# Carrier_Cancellation_HP.net
KiCad netlist of a schematic drawn in Altium Designer
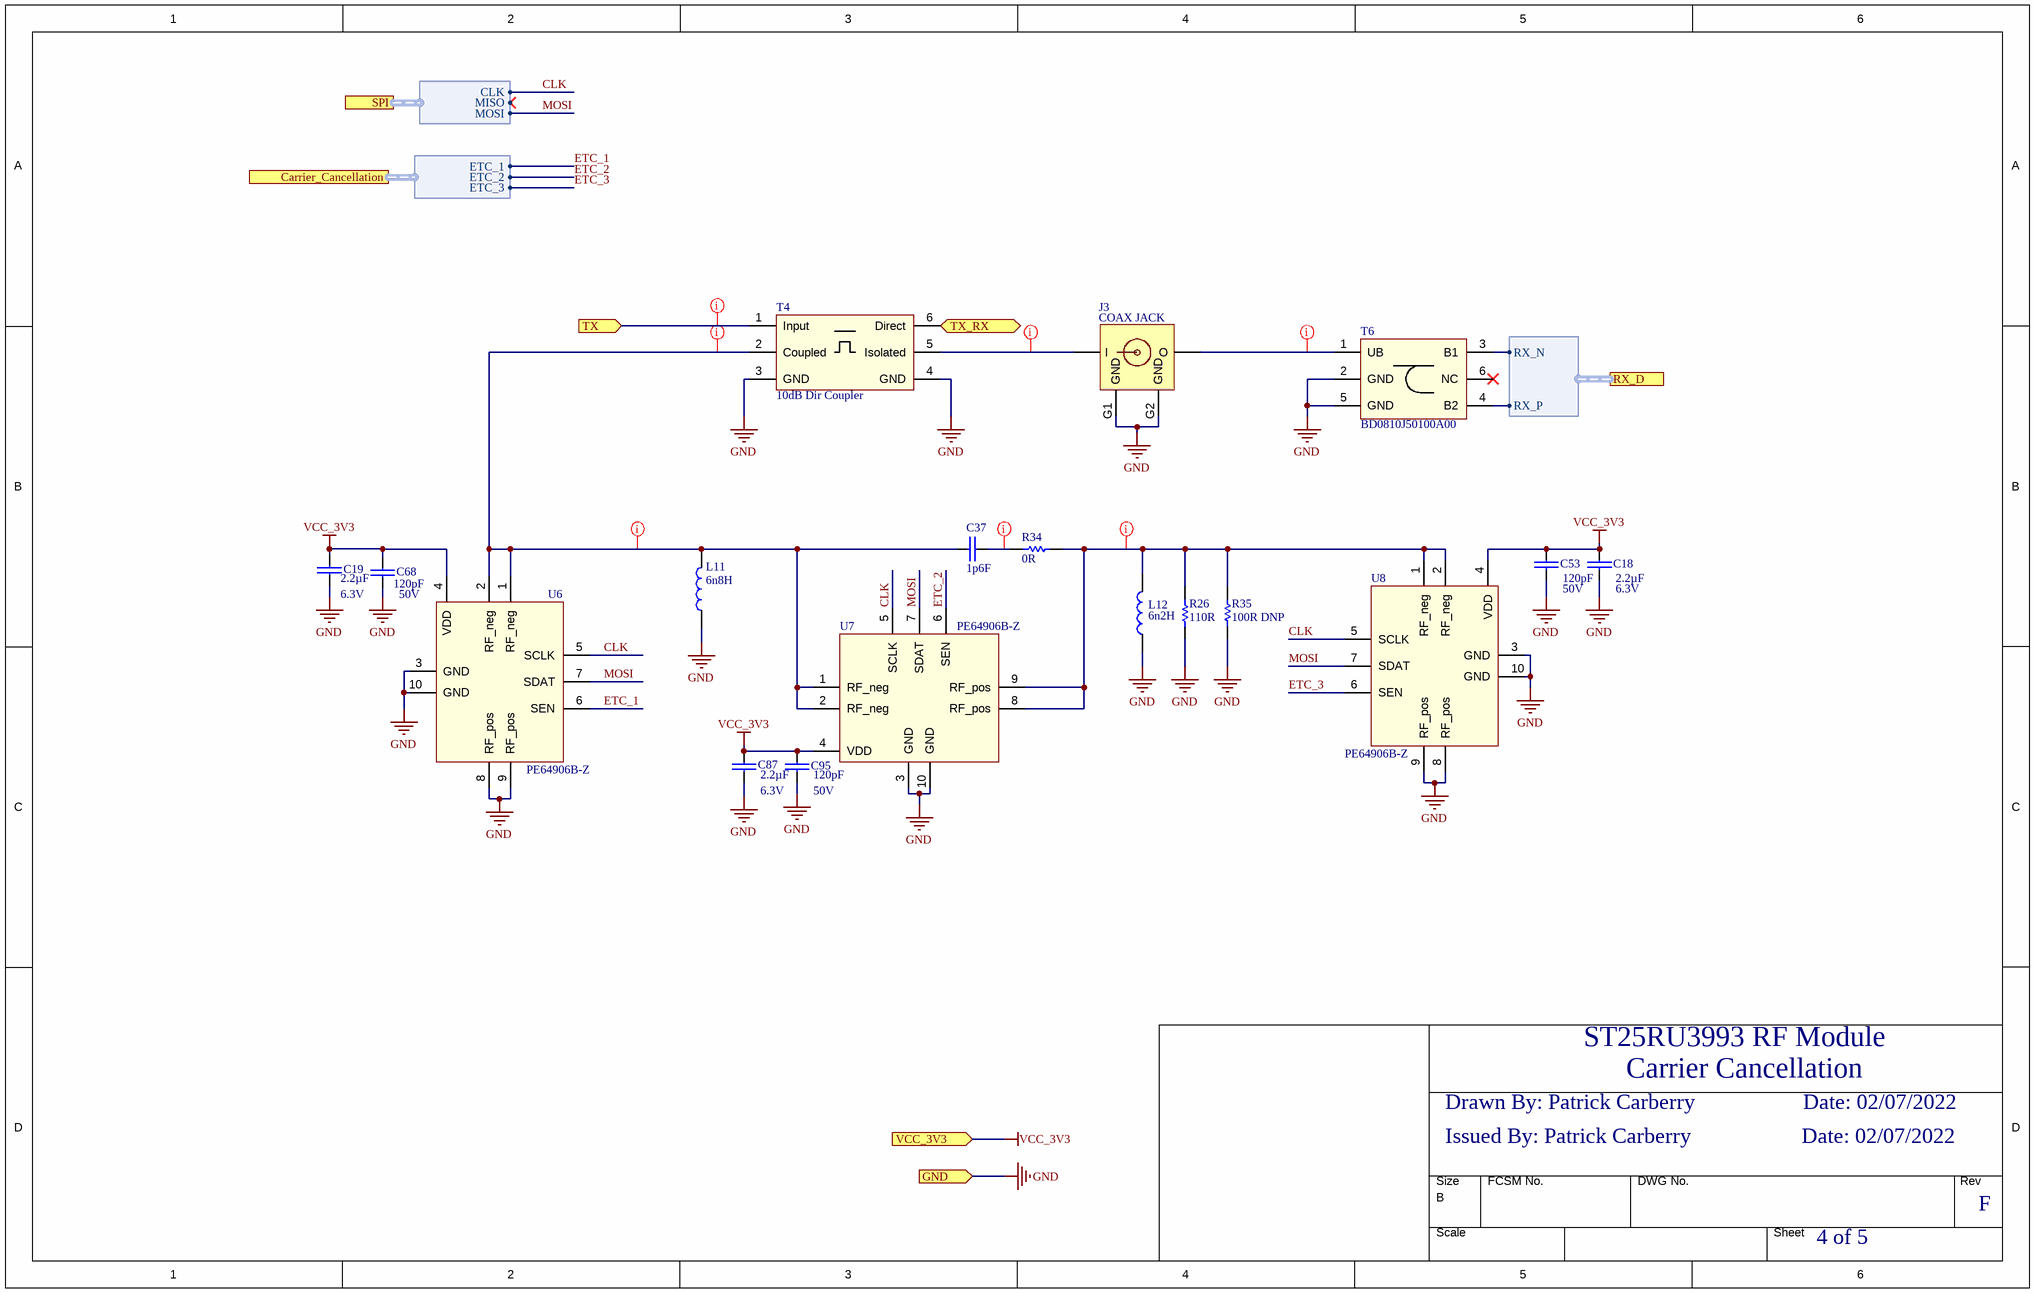
[diagram p0: Carrier_Cancellation_HP.SchDoc]

(export (version "E")
  (design (tool "Eeschema 10.0.6"))
  (components
    (comp (ref "C18")
      (value "C0402C225K9PAC7867")
      (footprint "C0402-RF")
      (description "CAP_2.2UF_6.3V_10%_X5R_0402")
      (fields
        (field (name "CAPACITANCE") "2.2µF")
        (field (name "TOLERANCE") "10%")
        (field (name "VOLTAGE - RATED") "6.3V")
        (field (name "MANUFACTURER") "KEMET")
      )
      (libsource (lib "ST25RU3993_RF_MODULE") (part "CAP_2.2UF_6.3V_10%_X5R_0402"))
    )
    (comp (ref "C19")
      (value "C0402C225K9PAC7867")
      (footprint "C0402-RF")
      (description "CAP_2.2UF_6.3V_10%_X5R_0402")
      (fields
        (field (name "CAPACITANCE") "2.2µF")
        (field (name "TOLERANCE") "10%")
        (field (name "VOLTAGE - RATED") "6.3V")
        (field (name "MANUFACTURER") "KEMET")
      )
      (libsource (lib "ST25RU3993_RF_MODULE") (part "CAP_2.2UF_6.3V_10%_X5R_0402"))
    )
    (comp (ref "C37")
      (value "1p6F")
      (footprint "C0402-RF")
      (fields
        (field (name "MANUFACTURER") "Murata")
        (field (name "MANUFACTURER PART NUMBER") "GRM1555C1H1R6BA01D")
      )
      (libsource (lib "ST25RU3993_Discovery_2V0") (part "GRM1555C1H3R6BA01D"))
    )
    (comp (ref "C53")
      (value "120pF")
      (footprint "C0402-RF")
      (description "CAP CER 120PF 50V C0G/NP0 0402")
      (fields
        (field (name "MANUFACTURER") "KEMET")
        (field (name "MANUFACTURER PART NUMBER") "C0402C121J5GACAUTO")
        (field (name "VOLTAGE") "50V")
      )
      (libsource (lib "ST25RU3993_RF_MODULE") (part "CAP_120PF_50V_5%_C0G_0402"))
    )
    (comp (ref "C68")
      (value "120pF")
      (footprint "C0402-RF")
      (description "CAP CER 120PF 50V C0G/NP0 0402")
      (fields
        (field (name "MANUFACTURER") "KEMET")
        (field (name "MANUFACTURER PART NUMBER") "C0402C121J5GACAUTO")
        (field (name "VOLTAGE") "50V")
      )
      (libsource (lib "ST25RU3993_RF_MODULE") (part "CAP_120PF_50V_5%_C0G_0402"))
    )
    (comp (ref "C87")
      (value "C0402C225K9PAC7867")
      (footprint "C0402-RF")
      (description "CAP_2.2UF_6.3V_10%_X5R_0402")
      (fields
        (field (name "CAPACITANCE") "2.2µF")
        (field (name "TOLERANCE") "10%")
        (field (name "VOLTAGE - RATED") "6.3V")
        (field (name "MANUFACTURER") "KEMET")
      )
      (libsource (lib "ST25RU3993_RF_MODULE") (part "CAP_2.2UF_6.3V_10%_X5R_0402"))
    )
    (comp (ref "C95")
      (value "120pF")
      (footprint "C0402-RF")
      (description "CAP CER 120PF 50V C0G/NP0 0402")
      (fields
        (field (name "MANUFACTURER") "KEMET")
        (field (name "MANUFACTURER PART NUMBER") "C0402C121J5GACAUTO")
        (field (name "VOLTAGE") "50V")
      )
      (libsource (lib "ST25RU3993_RF_MODULE") (part "CAP_120PF_50V_5%_C0G_0402"))
    )
    (comp (ref "J3")
      (value "COAX JACK")
      (footprint "MS-156HF")
      (description "CONN COAX JACK STR 50 OHM SMD")
      (fields
        (field (name "MANUFACTURER") "Hirose Electric Co Ltd")
        (field (name "MANUFACTURER PART NUMBER") "MS-156HF(01)")
      )
      (libsource (lib "ST25RU3993_Discovery_2V0") (part "MS-156HF"))
    )
    (comp (ref "L11")
      (value "6n8H")
      (footprint "L0402-RF")
      (description "FIXED IND 6.8NH 700MA 90 MOHM")
      (fields
        (field (name "MANUFACTURER") "Murata Electronics North America")
        (field (name "MANUFACTURER PART NUMBER") "LQW15AN6N8G00D")
      )
      (libsource (lib "ST25RU3993_Discovery_2V0") (part "LQW15AN6N8G00D"))
    )
    (comp (ref "L12")
      (value "6n2H")
      (footprint "L0402-RF")
      (description "Inductor RF Chip Wirewound 6.2nH 0.2nH 100MHz 25Q-Factor 700mA 90mOhm DCR 0402 T/R")
      (fields
        (field (name "MANUFACTURER") "Murata")
        (field (name "MANUFACTURER PART NUMBER") "LQW15AN6N2C00D")
      )
      (libsource (lib "ST25RU3993-EVAL") (part "LQW15AN5N6C10D"))
    )
    (comp (ref "R26")
      (value "110R")
      (footprint "R0402-RF")
      (description "RES SMD 110 OHM 1% 1/10W 0402")
      (fields
        (field (name "MANUFACTURER") "Panasonic")
        (field (name "MANUFACTURER PART NUMBER") "ERJ-2RKF1100X")
      )
      (libsource (lib "ST25RU3993-EVAL") (part "ERJ-2RKF75R0X"))
    )
    (comp (ref "R34")
      (value "0R")
      (footprint "R0402-RF")
      (description "RES SMD 0.0OHM JUMPER 1/16W 0402")
      (fields
        (field (name "MANUFACTURER") "Yageo")
        (field (name "MANUFACTURER PART NUMBER") "RC0402JR-070RL")
      )
      (libsource (lib "ST25RU3993_Discovery_2V0") (part "RC0402JR-070RL"))
    )
    (comp (ref "R35")
      (value "100R DNP")
      (footprint "R0402-RF")
      (description "RES SMD 100 OHM 1% 1/16W 0402")
      (fields
        (field (name "MANUFACTURER") "Yageo")
        (field (name "MANUFACTURER PART NUMBER") "RC0402FR-07100RL")
      )
      (libsource (lib "ST25RU3993_Discovery_2V0") (part "RC0402FR-07100RL"))
    )
    (comp (ref "T4")
      (value "10dB Dir Coupler")
      (footprint "DC0710J5010AHF")
      (description "Directional Coupler")
      (fields
        (field (name "MANUFACTURER") "Anaren")
        (field (name "MANUFACTURER PART NUMBER") "DC0710J5010AHF")
      )
      (libsource (lib "ST25RU3993-EVAL") (part "DC0710J5010AHF"))
    )
    (comp (ref "T6")
      (value "BD0810J50100A00")
      (footprint "BD0810J50100AHF")
      (description "XFRMR BALUN RF 800-1000MHZ 0805")
      (fields
        (field (name "MANUFACTURER") "Anaren")
        (field (name "MANUFACTURER PART NUMBER") "BD0810J50100AHF")
      )
      (libsource (lib "ST25RU3993-EVAL") (part "BD0810J50100AHF"))
    )
    (comp (ref "U6")
      (value "PE64906B-Z")
      (footprint "PE62304")
      (description "IC RF DTC 100-3000MHZ 10QFN")
      (fields (field (name "MANUFACTURER") "Peregrine Semiconductor"))
      (libsource (lib "") (part "PE64906MLAA-Z_2"))
    )
    (comp (ref "U7")
      (value "PE64906B-Z")
      (footprint "PE62304")
      (description "IC RF DTC 100-3000MHZ 10QFN")
      (fields (field (name "MANUFACTURER") "Peregrine Semiconductor"))
      (libsource (lib "ST25RU3993_Discovery_2V0") (part "PE64906MLAA-Z"))
    )
    (comp (ref "U8")
      (value "PE64906B-Z")
      (footprint "PE62304")
      (description "IC RF DTC 100-3000MHZ 10QFN")
      (fields (field (name "MANUFACTURER") "Peregrine Semiconductor"))
      (libsource (lib "") (part "PE64906MLAA-Z_1"))
    )
  )
  (nets
    (net (code "4") (name "/CLK") (class "Default")
      (node (ref "U6") (pin "5") (pinfunction "SCLK_5") (pintype "passive"))
      (node (ref "U7") (pin "5") (pinfunction "SCLK_5") (pintype "passive"))
      (node (ref "U8") (pin "5") (pinfunction "SCLK_5") (pintype "passive"))
    )
    (net (code "5") (name "/ETC_1") (class "Default")
      (node (ref "U6") (pin "6") (pinfunction "SEN_6") (pintype "passive"))
    )
    (net (code "6") (name "/ETC_2") (class "Default")
      (node (ref "U7") (pin "6") (pinfunction "SEN_6") (pintype "passive"))
    )
    (net (code "7") (name "/ETC_3") (class "Default")
      (node (ref "U8") (pin "6") (pinfunction "SEN_6") (pintype "passive"))
    )
    (net (code "8") (name "/MOSI") (class "Default")
      (node (ref "U6") (pin "7") (pinfunction "SDAT_7") (pintype "passive"))
      (node (ref "U7") (pin "7") (pinfunction "SDAT_7") (pintype "passive"))
      (node (ref "U8") (pin "7") (pinfunction "SDAT_7") (pintype "passive"))
    )
    (net (code "9") (name "/RX_N") (class "Default")
      (node (ref "T6") (pin "3") (pinfunction "B1_3") (pintype "passive"))
    )
    (net (code "10") (name "/RX_P") (class "Default")
      (node (ref "T6") (pin "4") (pinfunction "B2_4") (pintype "passive"))
    )
    (net (code "11") (name "/TX") (class "Default")
      (node (ref "T4") (pin "1") (pinfunction "Input_1") (pintype "passive"))
    )
    (net (code "12") (name "/TX_RX") (class "Default")
      (node (ref "T4") (pin "6") (pinfunction "Direct_6") (pintype "passive"))
    )
    (net (code "16") (name "GND") (class "Default")
      (node (ref "C18") (pin "2") (pinfunction "2_2") (pintype "passive"))
      (node (ref "C19") (pin "2") (pinfunction "2_2") (pintype "passive"))
      (node (ref "C53") (pin "2") (pinfunction "2_2") (pintype "passive"))
      (node (ref "C68") (pin "2") (pinfunction "2_2") (pintype "passive"))
      (node (ref "C87") (pin "2") (pinfunction "2_2") (pintype "passive"))
      (node (ref "C95") (pin "2") (pinfunction "2_2") (pintype "passive"))
      (node (ref "J3") (pin "G1") (pinfunction "GND_G1") (pintype "passive"))
      (node (ref "J3") (pin "G2") (pinfunction "GND_G2") (pintype "passive"))
      (node (ref "L11") (pin "1") (pinfunction "1_1") (pintype "passive"))
      (node (ref "L12") (pin "1") (pinfunction "1_1") (pintype "passive"))
      (node (ref "R26") (pin "1") (pinfunction "1_1") (pintype "passive"))
      (node (ref "R35") (pin "1") (pinfunction "1_1") (pintype "passive"))
      (node (ref "T4") (pin "3") (pinfunction "GND_3") (pintype "passive"))
      (node (ref "T4") (pin "4") (pinfunction "GND_4") (pintype "passive"))
      (node (ref "T6") (pin "2") (pinfunction "GND_2") (pintype "passive"))
      (node (ref "T6") (pin "5") (pinfunction "GND_5") (pintype "passive"))
      (node (ref "U6") (pin "10") (pinfunction "GND_10") (pintype "passive"))
      (node (ref "U6") (pin "3") (pinfunction "GND_3") (pintype "passive"))
      (node (ref "U6") (pin "8") (pinfunction "RF_pos_8") (pintype "passive"))
      (node (ref "U6") (pin "9") (pinfunction "RF_pos_9") (pintype "passive"))
      (node (ref "U7") (pin "10") (pinfunction "GND_10") (pintype "passive"))
      (node (ref "U7") (pin "3") (pinfunction "GND_3") (pintype "passive"))
      (node (ref "U8") (pin "10") (pinfunction "GND_10") (pintype "passive"))
      (node (ref "U8") (pin "3") (pinfunction "GND_3") (pintype "passive"))
      (node (ref "U8") (pin "8") (pinfunction "RF_pos_8") (pintype "passive"))
      (node (ref "U8") (pin "9") (pinfunction "RF_pos_9") (pintype "passive"))
    )
    (net (code "17") (name "Net-(C37-Pad2)") (class "Default")
      (node (ref "C37") (pin "2") (pinfunction "2_2") (pintype "passive"))
      (node (ref "R34") (pin "1") (pinfunction "1_1") (pintype "passive"))
    )
    (net (code "18") (name "Net-(J3-I)") (class "Default")
      (node (ref "J3") (pin "IN") (pinfunction "I_IN") (pintype "passive"))
      (node (ref "T4") (pin "5") (pinfunction "Isolated_5") (pintype "passive"))
    )
    (net (code "19") (name "Net-(J3-O)") (class "Default")
      (node (ref "J3") (pin "OUT") (pinfunction "O_OUT") (pintype "passive"))
      (node (ref "T6") (pin "1") (pinfunction "UB_1") (pintype "passive"))
    )
    (net (code "20") (name "Net-(L12-Pad2)") (class "Default")
      (node (ref "L12") (pin "2") (pinfunction "2_2") (pintype "passive"))
      (node (ref "R26") (pin "2") (pinfunction "2_2") (pintype "passive"))
      (node (ref "R34") (pin "2") (pinfunction "2_2") (pintype "passive"))
      (node (ref "R35") (pin "2") (pinfunction "2_2") (pintype "passive"))
      (node (ref "U7") (pin "8") (pinfunction "RF_pos_8") (pintype "passive"))
      (node (ref "U7") (pin "9") (pinfunction "RF_pos_9") (pintype "passive"))
      (node (ref "U8") (pin "1") (pinfunction "RF_neg_1") (pintype "passive"))
      (node (ref "U8") (pin "2") (pinfunction "RF_neg_2") (pintype "passive"))
    )
    (net (code "21") (name "Net-(T4-Coupled)") (class "Default")
      (node (ref "C37") (pin "1") (pinfunction "1_1") (pintype "passive"))
      (node (ref "L11") (pin "2") (pinfunction "2_2") (pintype "passive"))
      (node (ref "T4") (pin "2") (pinfunction "Coupled_2") (pintype "passive"))
      (node (ref "U6") (pin "1") (pinfunction "RF_neg_1") (pintype "passive"))
      (node (ref "U6") (pin "2") (pinfunction "RF_neg_2") (pintype "passive"))
      (node (ref "U7") (pin "1") (pinfunction "RF_neg_1") (pintype "passive"))
      (node (ref "U7") (pin "2") (pinfunction "RF_neg_2") (pintype "passive"))
    )
    (net (code "22") (name "VCC_3V3") (class "Default")
      (node (ref "C18") (pin "1") (pinfunction "1_1") (pintype "passive"))
      (node (ref "C19") (pin "1") (pinfunction "1_1") (pintype "passive"))
      (node (ref "C53") (pin "1") (pinfunction "1_1") (pintype "passive"))
      (node (ref "C68") (pin "1") (pinfunction "1_1") (pintype "passive"))
      (node (ref "C87") (pin "1") (pinfunction "1_1") (pintype "passive"))
      (node (ref "C95") (pin "1") (pinfunction "1_1") (pintype "passive"))
      (node (ref "U6") (pin "4") (pinfunction "VDD_4") (pintype "passive"))
      (node (ref "U7") (pin "4") (pinfunction "VDD_4") (pintype "passive"))
      (node (ref "U8") (pin "4") (pinfunction "VDD_4") (pintype "passive"))
    )
    (net (code "23") (name "unconnected-(T6-NC-Pad6)") (class "Default")
      (node (ref "T6") (pin "6") (pinfunction "NC_6") (pintype "passive+no_connect"))
    )
  )
)
